# Schematic.net
KiCad netlist of a schematic drawn in EAGLE
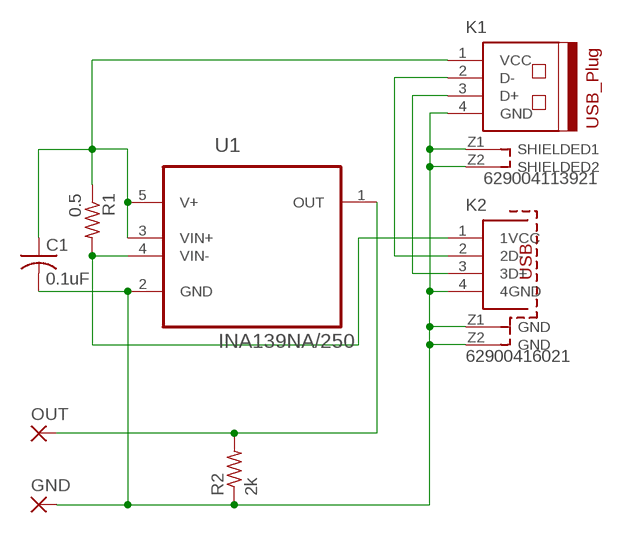
[diagram p0: schematic, sheet 1]

(export (version "E")
  (design (tool "Eeschema 10.0.6"))
  (components
    (comp (ref "C1")
      (value "0.1uF")
      (footprint "eagle-import:C1808")
      (libsource (lib "eagle-import") (part "C-USC1808"))
    )
    (comp (ref "GND")
      (value "2,54/1,0")
      (footprint "eagle-import:2,54_1,0")
      (libsource (lib "eagle-import") (part "2,54/1,0"))
    )
    (comp (ref "K1")
      (value "629004113921")
      (footprint "eagle-import:629004113921")
      (libsource (lib "eagle-import") (part "629004113921"))
    )
    (comp (ref "K2")
      (value "62900416021")
      (footprint "eagle-import:62900416021")
      (libsource (lib "eagle-import") (part "62900416021"))
    )
    (comp (ref "OUT")
      (value "2,54/1,0")
      (footprint "eagle-import:2,54_1,0")
      (libsource (lib "eagle-import") (part "2,54/1,0"))
    )
    (comp (ref "R1")
      (value "0.5")
      (footprint "eagle-import:R1206")
      (libsource (lib "eagle-import") (part "R-US_R1206"))
    )
    (comp (ref "R2")
      (value "2k")
      (footprint "eagle-import:R1206")
      (libsource (lib "eagle-import") (part "R-US_R1206"))
    )
    (comp (ref "U1")
      (value "INA139NA/250")
      (footprint "eagle-import:SOT95P280X145-5N")
      (libsource (lib "eagle-import") (part "INA139NA/250"))
    )
  )
  (nets
    (net (code "1") (name "Net-(GND-P)") (class "Default")
      (node (ref "C1") (pin "2") (pinfunction "2_2") (pintype "passive"))
      (node (ref "GND") (pin "1") (pinfunction "P_1") (pintype "passive"))
      (node (ref "K1") (pin "4") (pinfunction "GND_4") (pintype "passive"))
      (node (ref "K1") (pin "Z1") (pinfunction "SHIELDED1_Z1") (pintype "bidirectional"))
      (node (ref "K1") (pin "Z2") (pinfunction "SHIELDED2_Z2") (pintype "bidirectional"))
      (node (ref "K2") (pin "4") (pinfunction "4GND_4") (pintype "passive"))
      (node (ref "K2") (pin "Z1") (pinfunction "GND_Z1") (pintype "bidirectional"))
      (node (ref "K2") (pin "Z2") (pinfunction "GND_Z2") (pintype "bidirectional"))
      (node (ref "R2") (pin "1") (pinfunction "1_1") (pintype "passive"))
      (node (ref "U1") (pin "2") (pinfunction "GND_2") (pintype "passive"))
    )
    (net (code "2") (name "Net-(K1-D+)") (class "Default")
      (node (ref "K1") (pin "3") (pinfunction "D+_3") (pintype "passive"))
      (node (ref "K2") (pin "3") (pinfunction "3D+_3") (pintype "passive"))
    )
    (net (code "3") (name "Net-(K1-D-)") (class "Default")
      (node (ref "K1") (pin "2") (pinfunction "D-_2") (pintype "passive"))
      (node (ref "K2") (pin "2") (pinfunction "2D-_2") (pintype "passive"))
    )
    (net (code "4") (name "Net-(K1-VCC)") (class "Default")
      (node (ref "C1") (pin "1") (pinfunction "1_1") (pintype "passive"))
      (node (ref "K1") (pin "1") (pinfunction "VCC_1") (pintype "passive"))
      (node (ref "R1") (pin "1") (pinfunction "1_1") (pintype "passive"))
      (node (ref "U1") (pin "3") (pinfunction "VIN+_3") (pintype "input"))
      (node (ref "U1") (pin "5") (pinfunction "V+_5") (pintype "power_in"))
    )
    (net (code "5") (name "Net-(K2-1VCC)") (class "Default")
      (node (ref "K2") (pin "1") (pinfunction "1VCC_1") (pintype "passive"))
      (node (ref "R1") (pin "2") (pinfunction "2_2") (pintype "passive"))
      (node (ref "U1") (pin "4") (pinfunction "VIN-_4") (pintype "input"))
    )
    (net (code "6") (name "Net-(OUT-P)") (class "Default")
      (node (ref "OUT") (pin "1") (pinfunction "P_1") (pintype "passive"))
      (node (ref "R2") (pin "2") (pinfunction "2_2") (pintype "passive"))
      (node (ref "U1") (pin "1") (pinfunction "OUT_1") (pintype "output"))
    )
  )
)
